# Tesla_Giraffe.net
KiCad netlist of a schematic drawn in Altium Designer
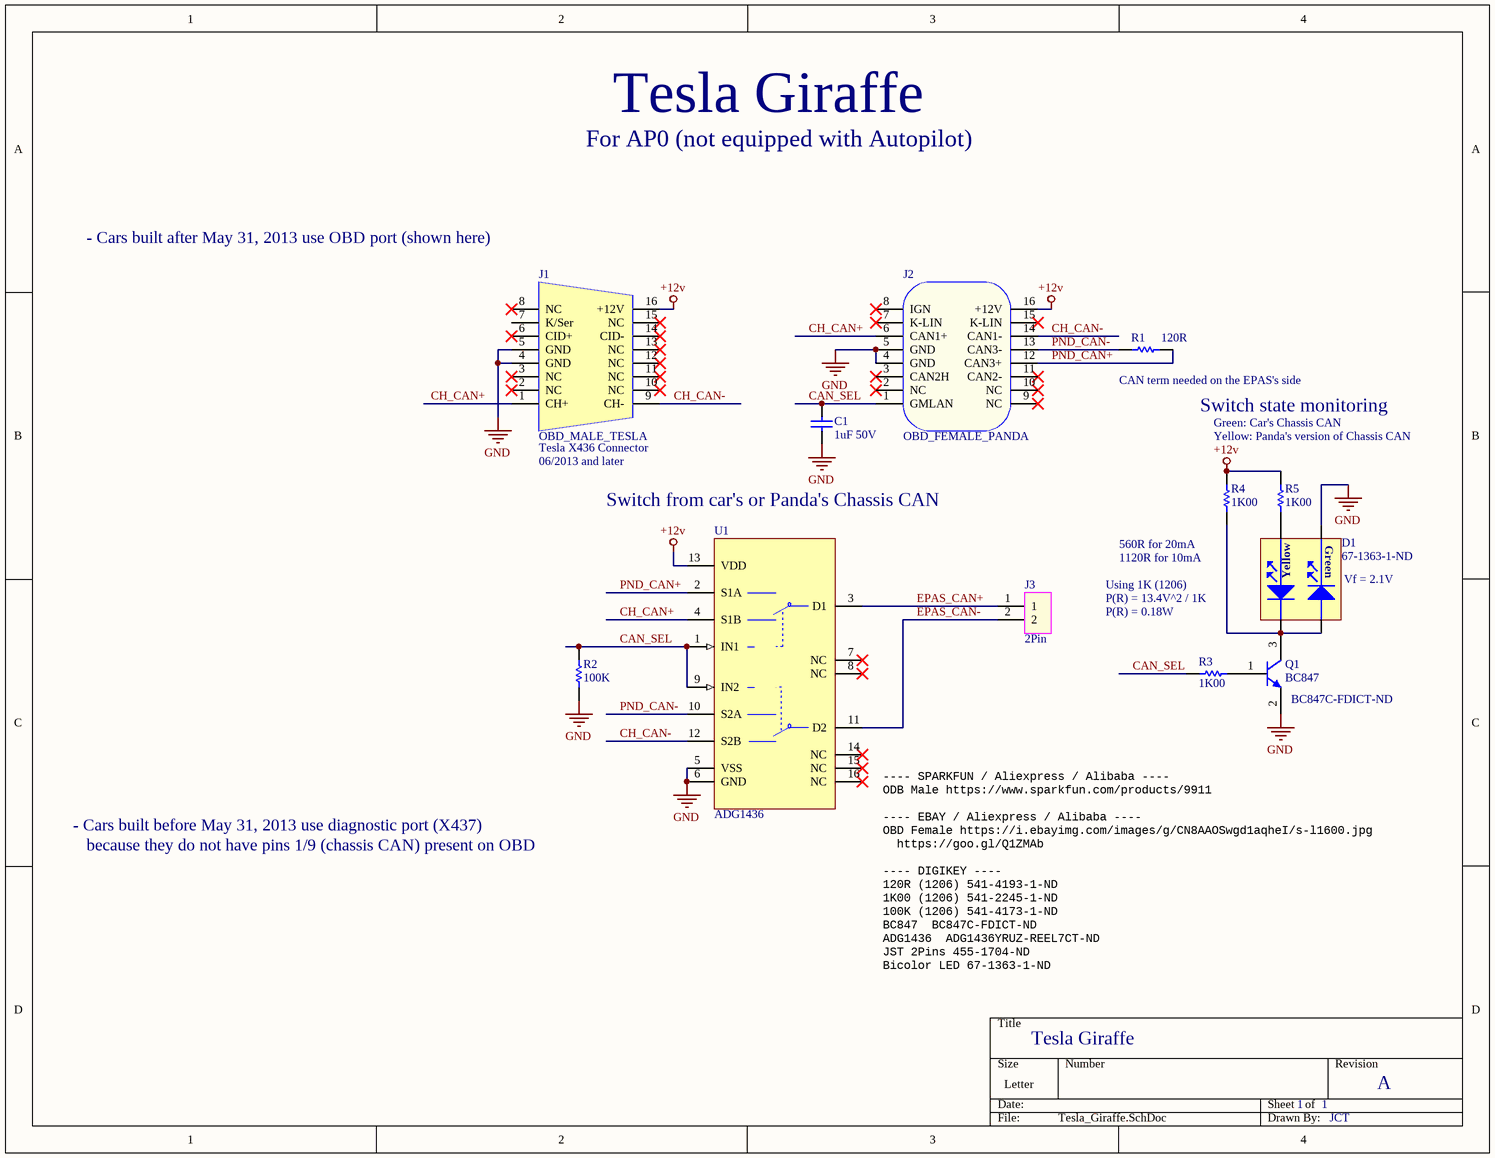
[diagram p0: Tesla_Giraffe.SchDoc]

(export (version "E")
  (design (tool "Eeschema 10.0.6"))
  (components
    (comp (ref "C1")
      (value "1uF 50V")
      (footprint "R_1206")
      (description "Capacitor (Semiconductor SIM Model)")
      (libsource (lib "parts") (part "CAPACITOR NP"))
    )
    (comp (ref "D1")
      (value "67-1363-1-ND")
      (footprint "LED_BICOLOR_1210")
      (description "SMD Dual (Green-Yellow) Led in a 1210 package")
      (fields (field (name "PART_NUMBER") "SML-LX1210YGC-TR") (field (name "MANUFACTURER") "Lumex"))
      (libsource (lib "Qtec_SVN") (part "LED_2_COL_LUMUX"))
    )
    (comp (ref "J1")
      (value "OBD_MALE_TESLA")
      (footprint "OBD_MALE")
      (description "OBD Male connector")
      (libsource (lib "parts") (part "OBD_MALE_TESLA"))
    )
    (comp (ref "J2")
      (value "OBD_FEMALE_PANDA")
      (footprint "OBD_FEMALE")
      (description "OBD Female connector")
      (libsource (lib "parts") (part "OBD_FEMALE_PANDA"))
    )
    (comp (ref "J3") (value "2Pin") (footprint "JST_PH_2PINS") (libsource (lib "parts") (part "2Pin")))
    (comp (ref "Q1")
      (value "BC847")
      (footprint "SOT23-3N")
      (description "NPN Bipolar Transistor")
      (libsource (lib "parts") (part "NPN"))
    )
    (comp (ref "R1")
      (value "120R")
      (footprint "R_1206")
      (description "Semiconductor Resistor")
      (libsource (lib "parts") (part "RESISTOR"))
    )
    (comp (ref "R2")
      (value "100K")
      (footprint "R_1206")
      (description "Semiconductor Resistor")
      (libsource (lib "parts") (part "RESISTOR"))
    )
    (comp (ref "R3")
      (value "1K00")
      (footprint "R_1206")
      (description "Semiconductor Resistor")
      (libsource (lib "parts") (part "RESISTOR"))
    )
    (comp (ref "R4")
      (value "1K00")
      (footprint "R_1206")
      (description "Semiconductor Resistor")
      (libsource (lib "parts") (part "RESISTOR"))
    )
    (comp (ref "R5")
      (value "1K00")
      (footprint "R_1206")
      (description "Semiconductor Resistor")
      (libsource (lib "parts") (part "RESISTOR"))
    )
    (comp (ref "U1")
      (value "ADG1436")
      (footprint "TSSOP16")
      (description "1.5 Ω On Resistance,  ±15 V/12 V/±5 V, iCMOS, Dual SPDT Switch")
      (libsource (lib "parts") (part "ADG1436"))
    )
  )
  (nets
    (net (code "1") (name "+12v") (class "Default")
      (node (ref "J1") (pin "16") (pinfunction "+12V_16") (pintype "passive"))
      (node (ref "J2") (pin "16") (pinfunction "+12V_16") (pintype "passive"))
      (node (ref "R4") (pin "2") (pinfunction "2_2") (pintype "passive"))
      (node (ref "R5") (pin "2") (pinfunction "2_2") (pintype "passive"))
      (node (ref "U1") (pin "13") (pinfunction "VDD_13") (pintype "power_in"))
    )
    (net (code "2") (name "/CAN_SEL") (class "Default")
      (node (ref "C1") (pin "2") (pinfunction "2_2") (pintype "passive"))
      (node (ref "J2") (pin "1") (pinfunction "GMLAN_1") (pintype "passive"))
      (node (ref "R2") (pin "2") (pinfunction "2_2") (pintype "passive"))
      (node (ref "R3") (pin "2") (pinfunction "2_2") (pintype "passive"))
      (node (ref "U1") (pin "1") (pinfunction "IN1_1") (pintype "input"))
      (node (ref "U1") (pin "9") (pinfunction "IN2_9") (pintype "input"))
    )
    (net (code "3") (name "/CH_CAN+") (class "Default")
      (node (ref "J1") (pin "1") (pinfunction "CH+_1") (pintype "passive"))
      (node (ref "J2") (pin "6") (pinfunction "CAN1+_6") (pintype "passive"))
      (node (ref "U1") (pin "4") (pinfunction "S1B_4") (pintype "passive"))
    )
    (net (code "4") (name "/CH_CAN-") (class "Default")
      (node (ref "J1") (pin "9") (pinfunction "CH-_9") (pintype "passive"))
      (node (ref "J2") (pin "14") (pinfunction "CAN1-_14") (pintype "passive"))
      (node (ref "U1") (pin "12") (pinfunction "S2B_12") (pintype "passive"))
    )
    (net (code "5") (name "/EPAS_CAN+") (class "Default")
      (node (ref "J3") (pin "1") (pinfunction "1_1") (pintype "passive"))
      (node (ref "U1") (pin "3") (pinfunction "D1_3") (pintype "passive"))
    )
    (net (code "6") (name "/EPAS_CAN-") (class "Default")
      (node (ref "J3") (pin "2") (pinfunction "2_2") (pintype "passive"))
      (node (ref "U1") (pin "11") (pinfunction "D2_11") (pintype "passive"))
    )
    (net (code "7") (name "/PND_CAN+") (class "Default")
      (node (ref "J2") (pin "12") (pinfunction "CAN3+_12") (pintype "passive"))
      (node (ref "R1") (pin "2") (pinfunction "2_2") (pintype "passive"))
      (node (ref "U1") (pin "2") (pinfunction "S1A_2") (pintype "passive"))
    )
    (net (code "8") (name "/PND_CAN-") (class "Default")
      (node (ref "J2") (pin "13") (pinfunction "CAN3-_13") (pintype "passive"))
      (node (ref "R1") (pin "1") (pinfunction "1_1") (pintype "passive"))
      (node (ref "U1") (pin "10") (pinfunction "S2A_10") (pintype "passive"))
    )
    (net (code "9") (name "GND") (class "Default")
      (node (ref "C1") (pin "1") (pinfunction "1_1") (pintype "passive"))
      (node (ref "D1") (pin "2C") (pinfunction "CATHODE2_2C") (pintype "passive"))
      (node (ref "J1") (pin "4") (pinfunction "GND_4") (pintype "passive"))
      (node (ref "J1") (pin "5") (pinfunction "GND_5") (pintype "passive"))
      (node (ref "J2") (pin "4") (pinfunction "GND_4") (pintype "passive"))
      (node (ref "J2") (pin "5") (pinfunction "GND_5") (pintype "passive"))
      (node (ref "Q1") (pin "2") (pinfunction "E_2") (pintype "passive"))
      (node (ref "R2") (pin "1") (pinfunction "1_1") (pintype "passive"))
      (node (ref "U1") (pin "5") (pinfunction "VSS_5") (pintype "power_in"))
      (node (ref "U1") (pin "6") (pinfunction "GND_6") (pintype "power_in"))
    )
    (net (code "10") (name "Net-(D1-ANODE1)") (class "Default")
      (node (ref "D1") (pin "1A") (pinfunction "ANODE1_1A") (pintype "passive"))
      (node (ref "R5") (pin "1") (pinfunction "1_1") (pintype "passive"))
    )
    (net (code "11") (name "Net-(D1-ANODE2)") (class "Default")
      (node (ref "D1") (pin "1C") (pinfunction "CATHODE1_1C") (pintype "passive"))
      (node (ref "D1") (pin "2A") (pinfunction "ANODE2_2A") (pintype "passive"))
      (node (ref "Q1") (pin "3") (pinfunction "C_3") (pintype "passive"))
      (node (ref "R4") (pin "1") (pinfunction "1_1") (pintype "passive"))
    )
    (net (code "12") (name "Net-(Q1-B)") (class "Default")
      (node (ref "Q1") (pin "1") (pinfunction "B_1") (pintype "passive"))
      (node (ref "R3") (pin "1") (pinfunction "1_1") (pintype "passive"))
    )
    (net (code "13") (name "unconnected-(J1-CID+-Pad6)") (class "Default")
      (node (ref "J1") (pin "6") (pinfunction "CID+_6") (pintype "passive+no_connect"))
    )
    (net (code "14") (name "unconnected-(J1-CID--Pad14)") (class "Default")
      (node (ref "J1") (pin "14") (pinfunction "CID-_14") (pintype "passive+no_connect"))
    )
    (net (code "15") (name "unconnected-(J1-K{slash}Ser-Pad7)") (class "Default")
      (node (ref "J1") (pin "7") (pinfunction "K/Ser_7") (pintype "passive"))
    )
    (net (code "16") (name "unconnected-(J1-NC-Pad2)") (class "Default")
      (node (ref "J1") (pin "2") (pinfunction "NC_2") (pintype "passive+no_connect"))
    )
    (net (code "17") (name "unconnected-(J1-NC-Pad3)") (class "Default")
      (node (ref "J1") (pin "3") (pinfunction "NC_3") (pintype "passive+no_connect"))
    )
    (net (code "18") (name "unconnected-(J1-NC-Pad8)") (class "Default")
      (node (ref "J1") (pin "8") (pinfunction "NC_8") (pintype "passive+no_connect"))
    )
    (net (code "19") (name "unconnected-(J1-NC-Pad10)") (class "Default")
      (node (ref "J1") (pin "10") (pinfunction "NC_10") (pintype "passive+no_connect"))
    )
    (net (code "20") (name "unconnected-(J1-NC-Pad11)") (class "Default")
      (node (ref "J1") (pin "11") (pinfunction "NC_11") (pintype "passive+no_connect"))
    )
    (net (code "21") (name "unconnected-(J1-NC-Pad12)") (class "Default")
      (node (ref "J1") (pin "12") (pinfunction "NC_12") (pintype "passive+no_connect"))
    )
    (net (code "22") (name "unconnected-(J1-NC-Pad13)") (class "Default")
      (node (ref "J1") (pin "13") (pinfunction "NC_13") (pintype "passive+no_connect"))
    )
    (net (code "23") (name "unconnected-(J1-NC-Pad15)") (class "Default")
      (node (ref "J1") (pin "15") (pinfunction "NC_15") (pintype "passive+no_connect"))
    )
    (net (code "24") (name "unconnected-(J2-CAN2--Pad11)") (class "Default")
      (node (ref "J2") (pin "11") (pinfunction "CAN2-_11") (pintype "passive+no_connect"))
    )
    (net (code "25") (name "unconnected-(J2-CAN2H-Pad3)") (class "Default")
      (node (ref "J2") (pin "3") (pinfunction "CAN2H_3") (pintype "passive+no_connect"))
    )
    (net (code "26") (name "unconnected-(J2-IGN-Pad8)") (class "Default")
      (node (ref "J2") (pin "8") (pinfunction "IGN_8") (pintype "passive+no_connect"))
    )
    (net (code "27") (name "unconnected-(J2-K-LIN-Pad7)") (class "Default")
      (node (ref "J2") (pin "7") (pinfunction "K-LIN_7") (pintype "passive+no_connect"))
    )
    (net (code "28") (name "unconnected-(J2-K-LIN-Pad15)") (class "Default")
      (node (ref "J2") (pin "15") (pinfunction "K-LIN_15") (pintype "passive+no_connect"))
    )
    (net (code "29") (name "unconnected-(J2-NC-Pad2)") (class "Default")
      (node (ref "J2") (pin "2") (pinfunction "NC_2") (pintype "passive+no_connect"))
    )
    (net (code "30") (name "unconnected-(J2-NC-Pad9)") (class "Default")
      (node (ref "J2") (pin "9") (pinfunction "NC_9") (pintype "passive+no_connect"))
    )
    (net (code "31") (name "unconnected-(J2-NC-Pad10)") (class "Default")
      (node (ref "J2") (pin "10") (pinfunction "NC_10") (pintype "passive+no_connect"))
    )
    (net (code "32") (name "unconnected-(U1-NC-Pad7)") (class "Default")
      (node (ref "U1") (pin "7") (pinfunction "NC_7") (pintype "passive+no_connect"))
    )
    (net (code "33") (name "unconnected-(U1-NC-Pad8)") (class "Default")
      (node (ref "U1") (pin "8") (pinfunction "NC_8") (pintype "passive+no_connect"))
    )
    (net (code "34") (name "unconnected-(U1-NC-Pad14)") (class "Default")
      (node (ref "U1") (pin "14") (pinfunction "NC_14") (pintype "passive+no_connect"))
    )
    (net (code "35") (name "unconnected-(U1-NC-Pad15)") (class "Default")
      (node (ref "U1") (pin "15") (pinfunction "NC_15") (pintype "passive+no_connect"))
    )
    (net (code "36") (name "unconnected-(U1-NC-Pad16)") (class "Default")
      (node (ref "U1") (pin "16") (pinfunction "NC_16") (pintype "passive+no_connect"))
    )
  )
)
